# LoRaSubsystem.net
KiCad netlist of a schematic drawn in Altium Designer
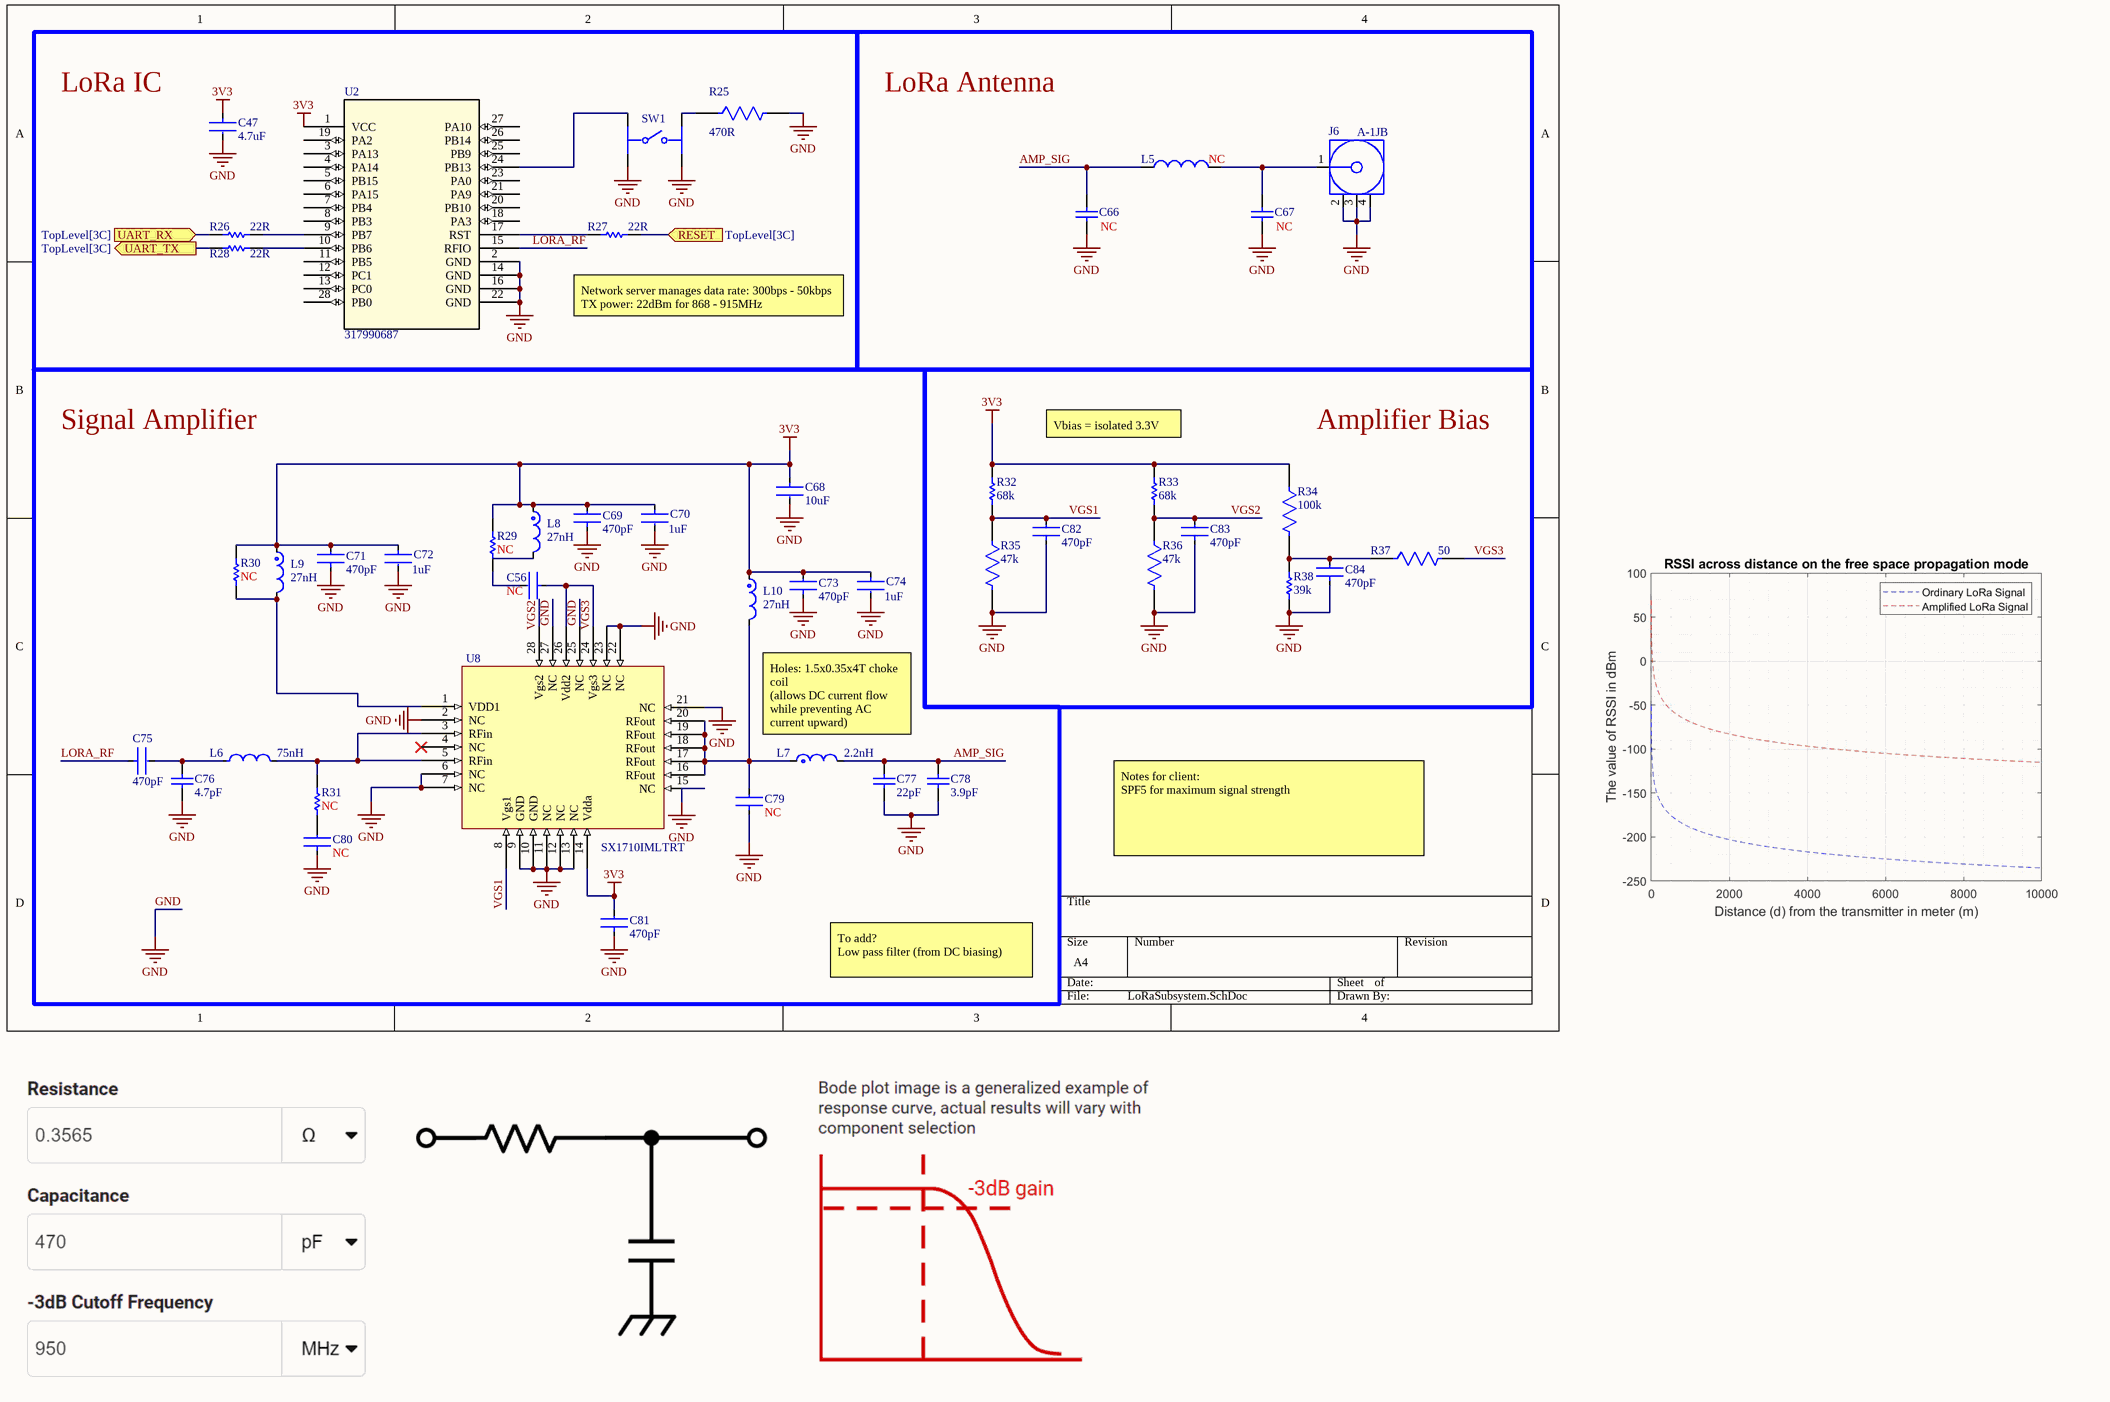
[diagram p0: LoRaSubsystem.SchDoc]

(export (version "E")
  (design (tool "Eeschema 10.0.6"))
  (components
    (comp (ref "C47")
      (value "4.7uF")
      (footprint "FP-C1005-050-0_15-MFG")
      (description "C1005X5R1A475K050BC")
      (fields (field (name "TOLERANCE") "10%"))
      (libsource (lib "Altium Content Vault") (part "b4654b650e69147ec39a6b967a45e02"))
    )
    (comp (ref "C56")
      (value "NC")
      (footprint "FP-C0603C-CF-MFG")
      (description "C0603C471K5RACTU")
      (fields (field (name "TOLERANCE") "0.1") (field (name "MANUFACTURER") "KEMET"))
      (libsource (lib "Altium Content Vault") (part "b4654b650e69147ec39a6b967a45e02"))
    )
    (comp (ref "C66")
      (value "NC")
      (footprint "CAPC1005X55X25LL05T10")
      (description "GRM1555C1H470JA01D")
      (fields (field (name "MANUFACTURER") "Murata"))
      (libsource (lib "Altium Content Vault") (part "CAP"))
    )
    (comp (ref "C67")
      (value "NC")
      (footprint "CAPC1005X55X25LL05T10")
      (description "GRM1555C1H470JA01D")
      (fields (field (name "MANUFACTURER") "Murata"))
      (libsource (lib "Altium Content Vault") (part "CAP"))
    )
    (comp (ref "C68")
      (value "10uF")
      (footprint "FP-GRM188-0_2-MFG")
      (description "Chip Multilayer Ceramic Capacitors for General Purpose, 0603, 10uF, X6S, 22%, 20%, 10V")
      (fields (field (name "TOLERANCE") "20%"))
      (libsource (lib "Altium Content Vault") (part "11868f565c42a9108669ba33697ecf6"))
    )
    (comp (ref "C69")
      (value "470pF")
      (footprint "FP-C0603C-CF-MFG")
      (description "C0603C471K5RACTU")
      (fields (field (name "TOLERANCE") "0.1") (field (name "MANUFACTURER") "KEMET"))
      (libsource (lib "Altium Content Vault") (part "b4654b650e69147ec39a6b967a45e02"))
    )
    (comp (ref "C70")
      (value "CL05A105KP5NNNC")
      (footprint "FP-CL511-IPC_C")
      (description "Cap Ceramic 1uF 10V X5R ±10% SMD 0402 +85°C Paper T/R")
      (fields (field (name "CAPACITANCE") "1uF") (field (name "TOLERANCE") "10%"))
      (libsource (lib "Altium Content Vault") (part "b4654b650e69147ec39a6b967a45e02"))
    )
    (comp (ref "C71")
      (value "470pF")
      (footprint "FP-C0603C-CF-MFG")
      (description "C0603C471K5RACTU")
      (fields (field (name "TOLERANCE") "0.1") (field (name "MANUFACTURER") "KEMET"))
      (libsource (lib "Altium Content Vault") (part "b4654b650e69147ec39a6b967a45e02"))
    )
    (comp (ref "C72")
      (value "CL05A105KP5NNNC")
      (footprint "FP-CL511-IPC_C")
      (description "Cap Ceramic 1uF 10V X5R ±10% SMD 0402 +85°C Paper T/R")
      (fields (field (name "CAPACITANCE") "1uF") (field (name "TOLERANCE") "10%"))
      (libsource (lib "Altium Content Vault") (part "b4654b650e69147ec39a6b967a45e02"))
    )
    (comp (ref "C73")
      (value "470pF")
      (footprint "FP-C0603C-CF-MFG")
      (description "C0603C471K5RACTU")
      (fields (field (name "TOLERANCE") "0.1") (field (name "MANUFACTURER") "KEMET"))
      (libsource (lib "Altium Content Vault") (part "b4654b650e69147ec39a6b967a45e02"))
    )
    (comp (ref "C74")
      (value "CL05A105KP5NNNC")
      (footprint "FP-CL511-IPC_C")
      (description "Cap Ceramic 1uF 10V X5R ±10% SMD 0402 +85°C Paper T/R")
      (fields (field (name "CAPACITANCE") "1uF") (field (name "TOLERANCE") "10%"))
      (libsource (lib "Altium Content Vault") (part "b4654b650e69147ec39a6b967a45e02"))
    )
    (comp (ref "C75")
      (value "470pF")
      (footprint "FP-C0603C-CF-MFG")
      (description "C0603C471K5RACTU")
      (fields (field (name "TOLERANCE") "0.1") (field (name "MANUFACTURER") "KEMET"))
      (libsource (lib "Altium Content Vault") (part "b4654b650e69147ec39a6b967a45e02"))
    )
    (comp (ref "C76")
      (value "4.7pF")
      (footprint "CAPC1006X50X20LL10T10")
      (description "04023J4R7BBSTR")
      (fields (field (name "MANUFACTURER") "AVX Interconnect / Elco"))
      (libsource (lib "Altium Content Vault") (part "CAP"))
    )
    (comp (ref "C77")
      (value "22pF")
      (footprint "CAPC1005X55X25NL05T10")
      (description "GRM1555C1H220JZ01D")
      (fields (field (name "MANUFACTURER") "Murata"))
      (libsource (lib "Altium Content Vault") (part "CAP"))
    )
    (comp (ref "C78")
      (value "3.9pF")
      (footprint "CAPC1006X50X20ML10T10")
      (description "04023J3R9BBSTR")
      (fields (field (name "MANUFACTURER") "AVX Interconnect / Elco"))
      (libsource (lib "Altium Content Vault") (part "CAP"))
    )
    (comp (ref "C79")
      (value "NC")
      (footprint "FP-C0603C-CF-MFG")
      (description "C0603C471K5RACTU")
      (fields (field (name "TOLERANCE") "0.1") (field (name "MANUFACTURER") "KEMET"))
      (libsource (lib "Altium Content Vault") (part "b4654b650e69147ec39a6b967a45e02"))
    )
    (comp (ref "C80")
      (value "NC")
      (footprint "FP-C0603C-CF-MFG")
      (description "C0603C471K5RACTU")
      (fields (field (name "TOLERANCE") "0.1") (field (name "MANUFACTURER") "KEMET"))
      (libsource (lib "Altium Content Vault") (part "b4654b650e69147ec39a6b967a45e02"))
    )
    (comp (ref "C81")
      (value "470pF")
      (footprint "FP-C0603C-CF-MFG")
      (description "C0603C471K5RACTU")
      (fields (field (name "TOLERANCE") "0.1") (field (name "MANUFACTURER") "KEMET"))
      (libsource (lib "Altium Content Vault") (part "b4654b650e69147ec39a6b967a45e02"))
    )
    (comp (ref "C82")
      (value "470pF")
      (footprint "FP-C0603C-CF-MFG")
      (description "C0603C471K5RACTU")
      (fields (field (name "TOLERANCE") "0.1") (field (name "MANUFACTURER") "KEMET"))
      (libsource (lib "Altium Content Vault") (part "b4654b650e69147ec39a6b967a45e02"))
    )
    (comp (ref "C83")
      (value "470pF")
      (footprint "FP-C0603C-CF-MFG")
      (description "C0603C471K5RACTU")
      (fields (field (name "TOLERANCE") "0.1") (field (name "MANUFACTURER") "KEMET"))
      (libsource (lib "Altium Content Vault") (part "b4654b650e69147ec39a6b967a45e02"))
    )
    (comp (ref "C84")
      (value "470pF")
      (footprint "FP-C0603C-CF-MFG")
      (description "C0603C471K5RACTU")
      (fields (field (name "TOLERANCE") "0.1") (field (name "MANUFACTURER") "KEMET"))
      (libsource (lib "Altium Content Vault") (part "b4654b650e69147ec39a6b967a45e02"))
    )
    (comp (ref "J6")
      (value "A-1JB")
      (footprint "AMPH-A-1JB_V")
      (description "AMC PCB Jack, 0 to 60 GHz, 60 V, -40 to 90 degC, 4-Pin SMD, RoHS, Tape and Reel")
      (fields (field (name "TOLERANCE") "10%"))
      (libsource (lib "Altium Content Vault") (part "CN-S-3F-RF4"))
    )
    (comp (ref "L5")
      (value "NC")
      (footprint "INDC1608X90X30LL10T20")
      (description "B82496C3330J")
      (fields (field (name "MANUFACTURER") "EPCOS-(TDK)") (field (name "TOLERANCE") "±5%"))
      (libsource (lib "Altium Content Vault") (part "IND-2"))
    )
    (comp (ref "L6")
      (value "75nH")
      (footprint "FP-LQW15AN_00-W0_5-0_1-MFG")
      (description "LQW15AN75NG00D")
      (fields (field (name "TOLERANCE") "2%"))
      (libsource (lib "Altium Content Vault") (part "725321dda6339637d4d059423bc1c3c"))
    )
    (comp (ref "L7")
      (value "2.2nH")
      (footprint "FP-LQG18HH_00-IPC_A")
      (description "LQG18HN2N2S00D")
      (libsource (lib "Altium Content Vault") (part "4cc4b267dca4c8e51f7102f422741d8"))
    )
    (comp (ref "L8")
      (value "27nH")
      (footprint "FP-LQG15HH_02-IPC_C")
      (description "LQG15HS27NJ02D")
      (fields (field (name "TOLERANCE") "5%"))
      (libsource (lib "Altium Content Vault") (part "4cc4b267dca4c8e51f7102f422741d8"))
    )
    (comp (ref "L9")
      (value "27nH")
      (footprint "FP-LQG15HH_02-IPC_C")
      (description "LQG15HS27NJ02D")
      (fields (field (name "TOLERANCE") "5%"))
      (libsource (lib "Altium Content Vault") (part "4cc4b267dca4c8e51f7102f422741d8"))
    )
    (comp (ref "L10")
      (value "27nH")
      (footprint "FP-LQG15HH_02-IPC_C")
      (description "LQG15HS27NJ02D")
      (fields (field (name "TOLERANCE") "5%"))
      (libsource (lib "Altium Content Vault") (part "4cc4b267dca4c8e51f7102f422741d8"))
    )
    (comp (ref "R25")
      (value "470R")
      (footprint "FP-CRCW0402-e3-MFG")
      (description "CRCW0402470RFKED")
      (fields (field (name "TOLERANCE") "1%"))
      (libsource (lib "Altium Content Vault") (part "1029c3af85768c4190bb7ad29bc67b5"))
    )
    (comp (ref "R26")
      (value "22R")
      (footprint "RESC1005X40X25LL05T05")
      (description "CRCW040222R0FKED")
      (fields (field (name "MANUFACTURER") "Vishay Dale"))
      (libsource (lib "Altium Content Vault") (part "RES"))
    )
    (comp (ref "R27")
      (value "22R")
      (footprint "RESC1005X40X25LL05T05")
      (description "CRCW040222R0FKED")
      (fields (field (name "MANUFACTURER") "Vishay Dale"))
      (libsource (lib "Altium Content Vault") (part "RES"))
    )
    (comp (ref "R28")
      (value "22R")
      (footprint "RESC1005X40X25LL05T05")
      (description "CRCW040222R0FKED")
      (fields (field (name "MANUFACTURER") "Vishay Dale"))
      (libsource (lib "Altium Content Vault") (part "RES"))
    )
    (comp (ref "R29")
      (value "NC")
      (footprint "RESC1609X50X30NL8T20")
      (description "CRCW060310K0FKEA")
      (fields (field (name "MANUFACTURER") "Vishay Semiconductor"))
      (libsource (lib "Altium Content Vault") (part "RES-2"))
    )
    (comp (ref "R30")
      (value "NC")
      (footprint "RESC1609X50X30NL8T20")
      (description "CRCW060310K0FKEA")
      (fields (field (name "MANUFACTURER") "Vishay Semiconductor"))
      (libsource (lib "Altium Content Vault") (part "RES-2"))
    )
    (comp (ref "R31")
      (value "NC")
      (footprint "RESC1609X50X30NL8T20")
      (description "CRCW060310K0FKEA")
      (fields (field (name "MANUFACTURER") "Vishay Semiconductor"))
      (libsource (lib "Altium Content Vault") (part "RES-2"))
    )
    (comp (ref "R32")
      (value "68k")
      (footprint "RESC2013X70X40NL20T20")
      (description "ERJ6ENF6802V")
      (fields (field (name "MANUFACTURER") "Panasonic"))
      (libsource (lib "Altium Content Vault") (part "RES"))
    )
    (comp (ref "R33")
      (value "68k")
      (footprint "RESC2013X70X40NL20T20")
      (description "ERJ6ENF6802V")
      (fields (field (name "MANUFACTURER") "Panasonic"))
      (libsource (lib "Altium Content Vault") (part "RES"))
    )
    (comp (ref "R34")
      (value "100k")
      (footprint "FP-ERA3A-IPC_A")
      (description "ERA-3AEB104V")
      (fields (field (name "TOLERANCE") "0.1%"))
      (libsource (lib "Altium Content Vault") (part "1029c3af85768c4190bb7ad29bc67b5"))
    )
    (comp (ref "R35")
      (value "47k")
      (footprint "FP-ERA6A-IPC_A")
      (description "ERA-6AEB473V")
      (fields (field (name "TOLERANCE") "0.1%"))
      (libsource (lib "Altium Content Vault") (part "1029c3af85768c4190bb7ad29bc67b5"))
    )
    (comp (ref "R36")
      (value "47k")
      (footprint "FP-ERA6A-IPC_A")
      (description "ERA-6AEB473V")
      (fields (field (name "TOLERANCE") "0.1%"))
      (libsource (lib "Altium Content Vault") (part "1029c3af85768c4190bb7ad29bc67b5"))
    )
    (comp (ref "R37")
      (value "50")
      (footprint "FP-FC0402-IPC_C")
      (description "FC0402E50R0BTBST1")
      (fields (field (name "TOLERANCE") "0.1%"))
      (libsource (lib "Altium Content Vault") (part "8db39607336c341a927600551d01821"))
    )
    (comp (ref "R38")
      (value "39k")
      (footprint "RESC1005X40X25LL05T05")
      (description "CRCW040239K0FKED")
      (fields (field (name "MANUFACTURER") "Vishay Dale"))
      (libsource (lib "Altium Content Vault") (part "RES"))
    )
    (comp (ref "SW1")
      (value "PTS645SM43SMTR92LFS")
      (footprint "FP-PTS645SM43SMTR92LFS-MFG")
      (description "SWITCH TACTILE SPST-NO 0.05A 12V")
      (libsource (lib "Altium Content Vault") (part "1adf0dd01260c80cf25a44bfd6b99ba"))
    )
    (comp (ref "U2")
      (value "317990687")
      (footprint "QFN_90687_SEE")
      (description "No Description Available")
      (libsource (lib "Hole") (part "317990687"))
    )
    (comp (ref "U8")
      (value "SX1710IMLTRT")
      (footprint "QFN50P500X500X100_HS-29N")
      (description "Broadband High Efficiency RF Power Amplifier")
      (libsource (lib "Team 11") (part "SX1710IMLTRT"))
    )
  )
  (nets
    (net (code "1") (name "/AMP_SIG") (class "Default")
      (node (ref "C66") (pin "2") (pinfunction "2_2") (pintype "passive"))
      (node (ref "C77") (pin "2") (pinfunction "2_2") (pintype "passive"))
      (node (ref "C78") (pin "2") (pinfunction "2_2") (pintype "passive"))
      (node (ref "L5") (pin "1") (pinfunction "1_1") (pintype "passive"))
      (node (ref "L7") (pin "2") (pinfunction "2_2") (pintype "passive"))
    )
    (net (code "2") (name "/LORA_RF") (class "Default")
      (node (ref "C75") (pin "1") (pinfunction "1_1") (pintype "passive"))
      (node (ref "U2") (pin "15") (pinfunction "RFIO_15") (pintype "passive"))
    )
    (net (code "3") (name "/RESET") (class "Default")
      (node (ref "R27") (pin "2") (pinfunction "2_2") (pintype "passive"))
    )
    (net (code "4") (name "/UART_RX") (class "Default")
      (node (ref "R26") (pin "1") (pinfunction "1_1") (pintype "passive"))
    )
    (net (code "5") (name "/UART_TX") (class "Default")
      (node (ref "R28") (pin "1") (pinfunction "1_1") (pintype "passive"))
    )
    (net (code "6") (name "/VGS1") (class "Default")
      (node (ref "C82") (pin "2") (pinfunction "2_2") (pintype "passive"))
      (node (ref "R32") (pin "1") (pinfunction "1_1") (pintype "passive"))
      (node (ref "R35") (pin "1") (pinfunction "1_1") (pintype "passive"))
      (node (ref "U8") (pin "8") (pinfunction "Vgs1_8") (pintype "input"))
    )
    (net (code "7") (name "/VGS2") (class "Default")
      (node (ref "C83") (pin "2") (pinfunction "2_2") (pintype "passive"))
      (node (ref "R33") (pin "1") (pinfunction "1_1") (pintype "passive"))
      (node (ref "R36") (pin "1") (pinfunction "1_1") (pintype "passive"))
      (node (ref "U8") (pin "28") (pinfunction "Vgs2_28") (pintype "input"))
    )
    (net (code "8") (name "/VGS3") (class "Default")
      (node (ref "C56") (pin "1") (pinfunction "1_1") (pintype "passive"))
      (node (ref "R37") (pin "2") (pinfunction "2_2") (pintype "passive"))
      (node (ref "U8") (pin "24") (pinfunction "Vgs3_24") (pintype "input"))
      (node (ref "U8") (pin "26") (pinfunction "Vdd2_26") (pintype "input"))
    )
    (net (code "9") (name "3V3") (class "Default")
      (node (ref "C47") (pin "1") (pinfunction "1_1") (pintype "passive"))
      (node (ref "C68") (pin "1") (pinfunction "1_1") (pintype "passive"))
      (node (ref "C69") (pin "2") (pinfunction "2_2") (pintype "passive"))
      (node (ref "C70") (pin "1") (pinfunction "1_1") (pintype "passive"))
      (node (ref "C71") (pin "2") (pinfunction "2_2") (pintype "passive"))
      (node (ref "C72") (pin "1") (pinfunction "1_1") (pintype "passive"))
      (node (ref "C73") (pin "2") (pinfunction "2_2") (pintype "passive"))
      (node (ref "C74") (pin "1") (pinfunction "1_1") (pintype "passive"))
      (node (ref "C81") (pin "2") (pinfunction "2_2") (pintype "passive"))
      (node (ref "L10") (pin "1") (pinfunction "1_1") (pintype "passive"))
      (node (ref "L8") (pin "1") (pinfunction "1_1") (pintype "passive"))
      (node (ref "L9") (pin "1") (pinfunction "1_1") (pintype "passive"))
      (node (ref "R29") (pin "2") (pinfunction "2_2") (pintype "passive"))
      (node (ref "R30") (pin "2") (pinfunction "2_2") (pintype "passive"))
      (node (ref "R32") (pin "2") (pinfunction "2_2") (pintype "passive"))
      (node (ref "R33") (pin "2") (pinfunction "2_2") (pintype "passive"))
      (node (ref "R34") (pin "1") (pinfunction "1_1") (pintype "passive"))
      (node (ref "U2") (pin "1") (pinfunction "VCC_1") (pintype "power_in"))
      (node (ref "U8") (pin "14") (pinfunction "Vdda_14") (pintype "input"))
    )
    (net (code "10") (name "GND") (class "Default")
      (node (ref "C47") (pin "2") (pinfunction "2_2") (pintype "passive"))
      (node (ref "C66") (pin "1") (pinfunction "1_1") (pintype "passive"))
      (node (ref "C67") (pin "1") (pinfunction "1_1") (pintype "passive"))
      (node (ref "C68") (pin "2") (pinfunction "2_2") (pintype "passive"))
      (node (ref "C69") (pin "1") (pinfunction "1_1") (pintype "passive"))
      (node (ref "C70") (pin "2") (pinfunction "2_2") (pintype "passive"))
      (node (ref "C71") (pin "1") (pinfunction "1_1") (pintype "passive"))
      (node (ref "C72") (pin "2") (pinfunction "2_2") (pintype "passive"))
      (node (ref "C73") (pin "1") (pinfunction "1_1") (pintype "passive"))
      (node (ref "C74") (pin "2") (pinfunction "2_2") (pintype "passive"))
      (node (ref "C76") (pin "1") (pinfunction "1_1") (pintype "passive"))
      (node (ref "C77") (pin "1") (pinfunction "1_1") (pintype "passive"))
      (node (ref "C78") (pin "1") (pinfunction "1_1") (pintype "passive"))
      (node (ref "C79") (pin "1") (pinfunction "1_1") (pintype "passive"))
      (node (ref "C80") (pin "1") (pinfunction "1_1") (pintype "passive"))
      (node (ref "C81") (pin "1") (pinfunction "1_1") (pintype "passive"))
      (node (ref "C82") (pin "1") (pinfunction "1_1") (pintype "passive"))
      (node (ref "C83") (pin "1") (pinfunction "1_1") (pintype "passive"))
      (node (ref "C84") (pin "1") (pinfunction "1_1") (pintype "passive"))
      (node (ref "J6") (pin "2") (pinfunction "2_2") (pintype "passive"))
      (node (ref "J6") (pin "3") (pinfunction "3_3") (pintype "passive"))
      (node (ref "J6") (pin "4") (pinfunction "4_4") (pintype "passive"))
      (node (ref "R25") (pin "2") (pinfunction "2_2") (pintype "passive"))
      (node (ref "R35") (pin "2") (pinfunction "2_2") (pintype "passive"))
      (node (ref "R36") (pin "2") (pinfunction "2_2") (pintype "passive"))
      (node (ref "R38") (pin "2") (pinfunction "2_2") (pintype "passive"))
      (node (ref "SW1") (pin "2") (pinfunction "2_2") (pintype "passive"))
      (node (ref "SW1") (pin "4") (pinfunction "4_4") (pintype "passive"))
      (node (ref "U2") (pin "14") (pinfunction "GND_14") (pintype "power_in"))
      (node (ref "U2") (pin "16") (pinfunction "GND_16") (pintype "power_in"))
      (node (ref "U2") (pin "2") (pinfunction "GND_2") (pintype "power_in"))
      (node (ref "U2") (pin "22") (pinfunction "GND_22") (pintype "power_in"))
      (node (ref "U8") (pin "10") (pinfunction "GND_10") (pintype "input"))
      (node (ref "U8") (pin "11") (pinfunction "NC_11") (pintype "input"))
      (node (ref "U8") (pin "12") (pinfunction "NC_12") (pintype "input"))
      (node (ref "U8") (pin "13") (pinfunction "NC_13") (pintype "input"))
      (node (ref "U8") (pin "15") (pinfunction "NC_15") (pintype "input"))
      (node (ref "U8") (pin "2") (pinfunction "NC_2") (pintype "input"))
      (node (ref "U8") (pin "21") (pinfunction "NC_21") (pintype "input"))
      (node (ref "U8") (pin "22") (pinfunction "NC_22") (pintype "input"))
      (node (ref "U8") (pin "23") (pinfunction "NC_23") (pintype "input"))
      (node (ref "U8") (pin "25") (pinfunction "NC_25") (pintype "input"))
      (node (ref "U8") (pin "27") (pinfunction "NC_27") (pintype "input"))
      (node (ref "U8") (pin "6") (pinfunction "NC_6") (pintype "input"))
      (node (ref "U8") (pin "7") (pinfunction "NC_7") (pintype "input"))
      (node (ref "U8") (pin "9") (pinfunction "GND_9") (pintype "input"))
    )
    (net (code "11") (name "Net-(C56-Pad2)") (class "Default")
      (node (ref "C56") (pin "2") (pinfunction "2_2") (pintype "passive"))
      (node (ref "R29") (pin "1") (pinfunction "1_1") (pintype "passive"))
    )
    (net (code "12") (name "Net-(C67-Pad2)") (class "Default")
      (node (ref "C67") (pin "2") (pinfunction "2_2") (pintype "passive"))
      (node (ref "J6") (pin "1") (pinfunction "1_1") (pintype "passive"))
      (node (ref "L5") (pin "2") (pinfunction "2_2") (pintype "passive"))
    )
    (net (code "13") (name "Net-(C75-Pad2)") (class "Default")
      (node (ref "C75") (pin "2") (pinfunction "2_2") (pintype "passive"))
      (node (ref "C76") (pin "2") (pinfunction "2_2") (pintype "passive"))
      (node (ref "L6") (pin "1") (pinfunction "1_1") (pintype "passive"))
    )
    (net (code "14") (name "Net-(C79-Pad2)") (class "Default")
      (node (ref "C79") (pin "2") (pinfunction "2_2") (pintype "passive"))
      (node (ref "L10") (pin "2") (pinfunction "2_2") (pintype "passive"))
      (node (ref "L7") (pin "1") (pinfunction "1_1") (pintype "passive"))
      (node (ref "U8") (pin "16") (pinfunction "RFout_16") (pintype "input"))
      (node (ref "U8") (pin "17") (pinfunction "RFout_17") (pintype "input"))
      (node (ref "U8") (pin "18") (pinfunction "RFout_18") (pintype "input"))
      (node (ref "U8") (pin "19") (pinfunction "RFout_19") (pintype "input"))
      (node (ref "U8") (pin "20") (pinfunction "RFout_20") (pintype "input"))
    )
    (net (code "15") (name "Net-(C80-Pad2)") (class "Default")
      (node (ref "C80") (pin "2") (pinfunction "2_2") (pintype "passive"))
      (node (ref "R31") (pin "1") (pinfunction "1_1") (pintype "passive"))
    )
    (net (code "16") (name "Net-(C84-Pad2)") (class "Default")
      (node (ref "C84") (pin "2") (pinfunction "2_2") (pintype "passive"))
      (node (ref "R34") (pin "2") (pinfunction "2_2") (pintype "passive"))
      (node (ref "R37") (pin "1") (pinfunction "1_1") (pintype "passive"))
      (node (ref "R38") (pin "1") (pinfunction "1_1") (pintype "passive"))
    )
    (net (code "17") (name "Net-(L6-Pad2)") (class "Default")
      (node (ref "L6") (pin "2") (pinfunction "2_2") (pintype "passive"))
      (node (ref "R31") (pin "2") (pinfunction "2_2") (pintype "passive"))
      (node (ref "U8") (pin "3") (pinfunction "RFin_3") (pintype "input"))
      (node (ref "U8") (pin "5") (pinfunction "RFin_5") (pintype "input"))
    )
    (net (code "18") (name "Net-(R25-Pad1)") (class "Default")
      (node (ref "R25") (pin "1") (pinfunction "1_1") (pintype "passive"))
      (node (ref "SW1") (pin "1") (pinfunction "1_1") (pintype "passive"))
    )
    (net (code "19") (name "Net-(U2-PB6)") (class "Default")
      (node (ref "R28") (pin "2") (pinfunction "2_2") (pintype "passive"))
      (node (ref "U2") (pin "10") (pinfunction "PB6_10") (pintype "bidirectional"))
    )
    (net (code "20") (name "Net-(U2-PB7)") (class "Default")
      (node (ref "R26") (pin "2") (pinfunction "2_2") (pintype "passive"))
      (node (ref "U2") (pin "9") (pinfunction "PB7_9") (pintype "bidirectional"))
    )
    (net (code "21") (name "Net-(U2-PB13)") (class "Default")
      (node (ref "SW1") (pin "3") (pinfunction "3_3") (pintype "passive"))
      (node (ref "U2") (pin "24") (pinfunction "PB13_24") (pintype "bidirectional"))
    )
    (net (code "22") (name "Net-(U2-RST)") (class "Default")
      (node (ref "R27") (pin "1") (pinfunction "1_1") (pintype "passive"))
      (node (ref "U2") (pin "17") (pinfunction "RST_17") (pintype "passive"))
    )
    (net (code "23") (name "Net-(U8-VDD1)") (class "Default")
      (node (ref "L9") (pin "2") (pinfunction "2_2") (pintype "passive"))
      (node (ref "R30") (pin "1") (pinfunction "1_1") (pintype "passive"))
      (node (ref "U8") (pin "1") (pinfunction "VDD1_1") (pintype "input"))
    )
    (net (code "24") (name "unconnected-(L8-Pad2)") (class "Default")
      (node (ref "L8") (pin "2") (pinfunction "2_2") (pintype "passive"))
    )
    (net (code "25") (name "unconnected-(U2-PA0-Pad23)") (class "Default")
      (node (ref "U2") (pin "23") (pinfunction "PA0_23") (pintype "bidirectional"))
    )
    (net (code "26") (name "unconnected-(U2-PA2-Pad19)") (class "Default")
      (node (ref "U2") (pin "19") (pinfunction "PA2_19") (pintype "bidirectional"))
    )
    (net (code "27") (name "unconnected-(U2-PA3-Pad18)") (class "Default")
      (node (ref "U2") (pin "18") (pinfunction "PA3_18") (pintype "bidirectional"))
    )
    (net (code "28") (name "unconnected-(U2-PA9-Pad21)") (class "Default")
      (node (ref "U2") (pin "21") (pinfunction "PA9_21") (pintype "bidirectional"))
    )
    (net (code "29") (name "unconnected-(U2-PA10-Pad27)") (class "Default")
      (node (ref "U2") (pin "27") (pinfunction "PA10_27") (pintype "bidirectional"))
    )
    (net (code "30") (name "unconnected-(U2-PA13-Pad3)") (class "Default")
      (node (ref "U2") (pin "3") (pinfunction "PA13_3") (pintype "bidirectional"))
    )
    (net (code "31") (name "unconnected-(U2-PA14-Pad4)") (class "Default")
      (node (ref "U2") (pin "4") (pinfunction "PA14_4") (pintype "bidirectional"))
    )
    (net (code "32") (name "unconnected-(U2-PA15-Pad6)") (class "Default")
      (node (ref "U2") (pin "6") (pinfunction "PA15_6") (pintype "bidirectional"))
    )
    (net (code "33") (name "unconnected-(U2-PB0-Pad28)") (class "Default")
      (node (ref "U2") (pin "28") (pinfunction "PB0_28") (pintype "bidirectional"))
    )
    (net (code "34") (name "unconnected-(U2-PB3-Pad8)") (class "Default")
      (node (ref "U2") (pin "8") (pinfunction "PB3_8") (pintype "bidirectional"))
    )
    (net (code "35") (name "unconnected-(U2-PB4-Pad7)") (class "Default")
      (node (ref "U2") (pin "7") (pinfunction "PB4_7") (pintype "bidirectional"))
    )
    (net (code "36") (name "unconnected-(U2-PB5-Pad11)") (class "Default")
      (node (ref "U2") (pin "11") (pinfunction "PB5_11") (pintype "bidirectional"))
    )
    (net (code "37") (name "unconnected-(U2-PB9-Pad25)") (class "Default")
      (node (ref "U2") (pin "25") (pinfunction "PB9_25") (pintype "bidirectional"))
    )
    (net (code "38") (name "unconnected-(U2-PB10-Pad20)") (class "Default")
      (node (ref "U2") (pin "20") (pinfunction "PB10_20") (pintype "bidirectional"))
    )
    (net (code "39") (name "unconnected-(U2-PB14-Pad26)") (class "Default")
      (node (ref "U2") (pin "26") (pinfunction "PB14_26") (pintype "bidirectional"))
    )
    (net (code "40") (name "unconnected-(U2-PB15-Pad5)") (class "Default")
      (node (ref "U2") (pin "5") (pinfunction "PB15_5") (pintype "bidirectional"))
    )
    (net (code "41") (name "unconnected-(U2-PC0-Pad13)") (class "Default")
      (node (ref "U2") (pin "13") (pinfunction "PC0_13") (pintype "bidirectional"))
    )
    (net (code "42") (name "unconnected-(U2-PC1-Pad12)") (class "Default")
      (node (ref "U2") (pin "12") (pinfunction "PC1_12") (pintype "bidirectional"))
    )
    (net (code "43") (name "unconnected-(U8-NC-Pad4)") (class "Default")
      (node (ref "U8") (pin "4") (pinfunction "NC_4") (pintype "input+no_connect"))
    )
  )
)
